# Tengu_v10.net
KiCad netlist of a schematic drawn in EAGLE
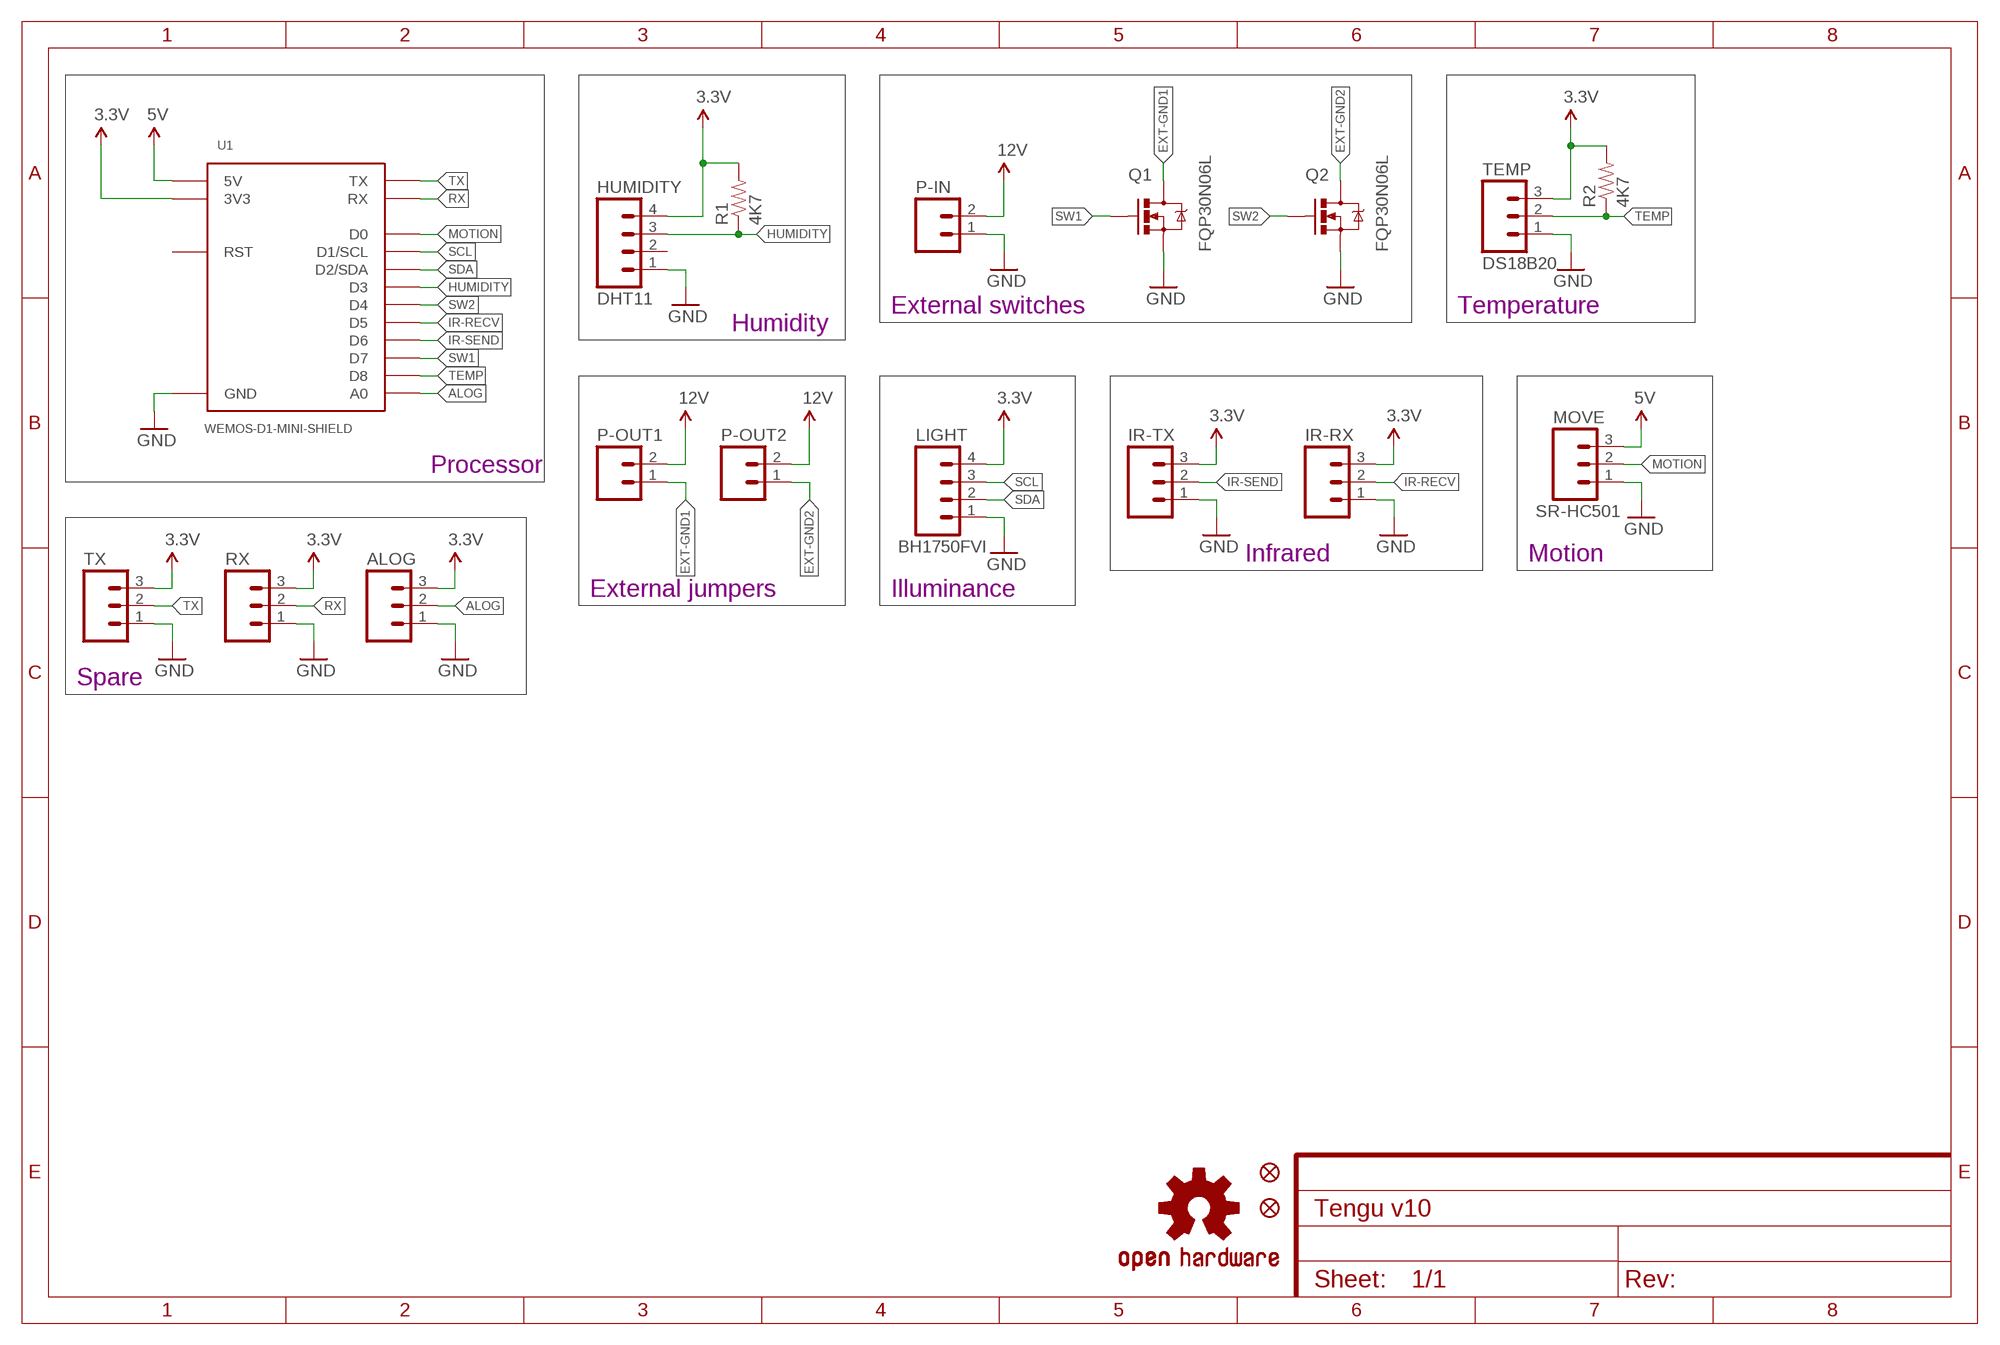
[diagram p0: schematic, sheet 1, part 1 of 2]
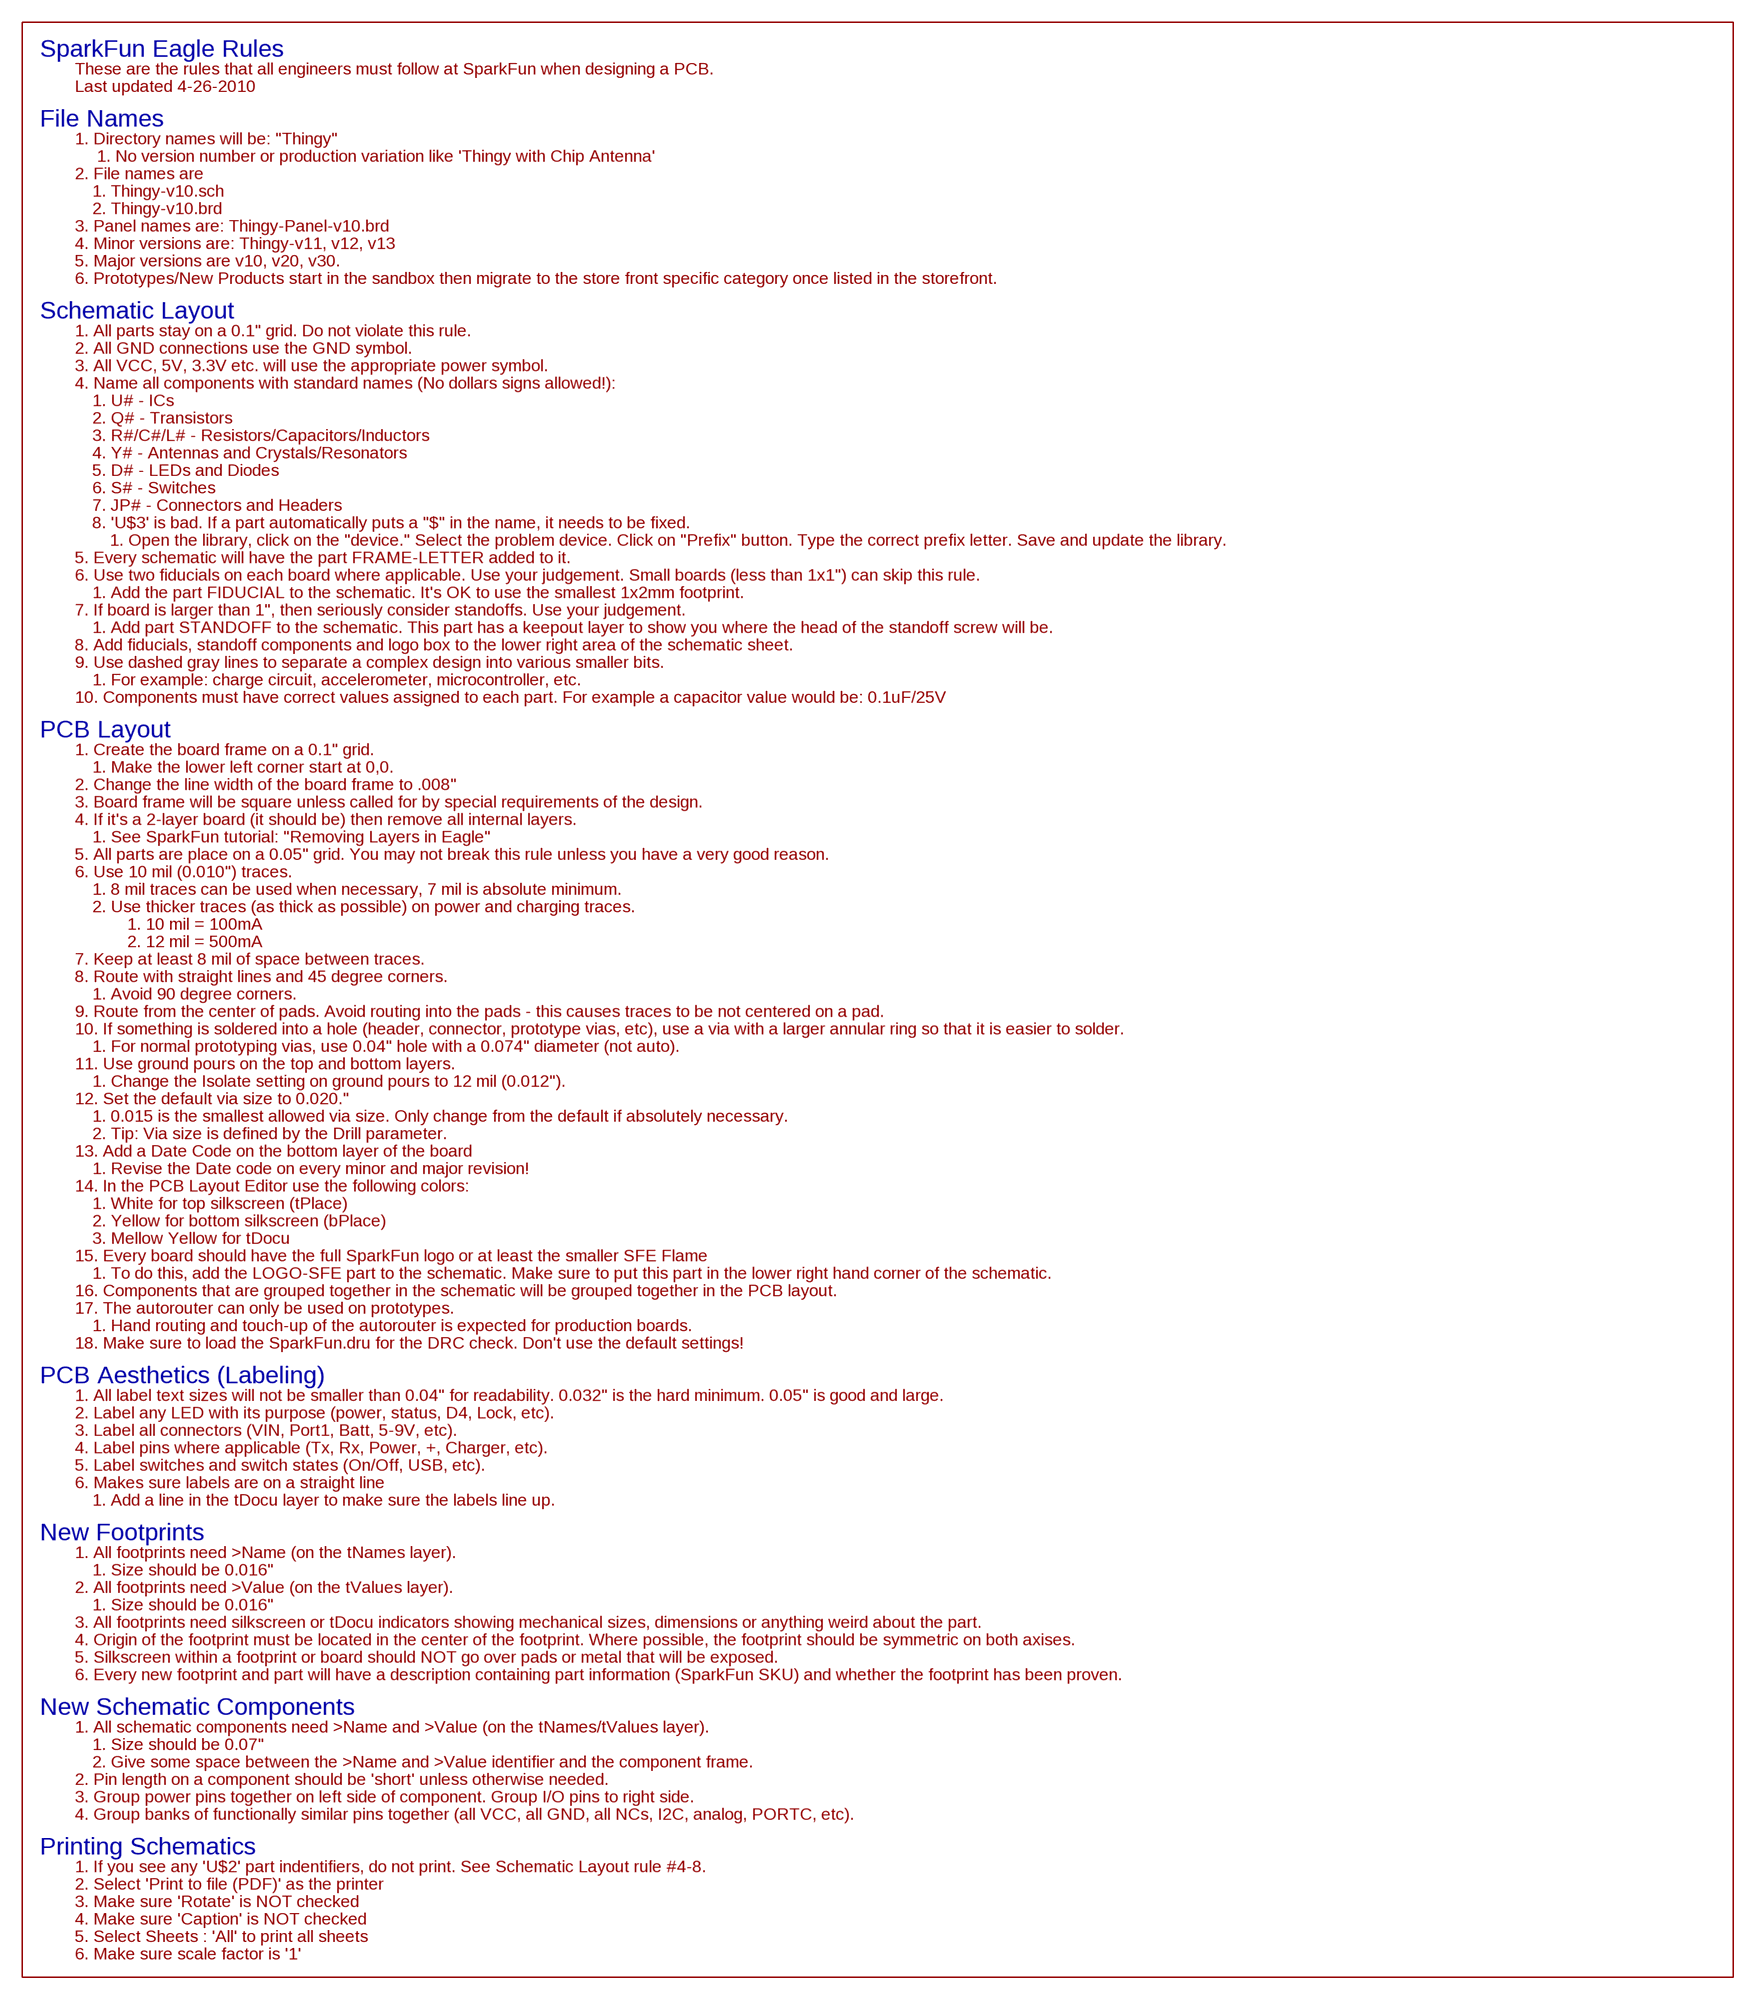
[diagram p1: schematic, sheet 1, part 2 of 2]

(export (version "E")
  (design (tool "Eeschema 10.0.6"))
  (components
    (comp (ref "ALOG")
      (value "M03PTH")
      (footprint "eagle-import:1X03")
      (libsource (lib "eagle-import") (part "M03PTH"))
    )
    (comp (ref "FD1")
      (value "FIDUCIAL1X2")
      (footprint "eagle-import:FIDUCIAL-1X2")
      (libsource (lib "eagle-import") (part "FIDUCIAL1X2"))
    )
    (comp (ref "FD2")
      (value "FIDUCIAL1X2")
      (footprint "eagle-import:FIDUCIAL-1X2")
      (libsource (lib "eagle-import") (part "FIDUCIAL1X2"))
    )
    (comp (ref "HUMIDITY")
      (value "DHT11")
      (footprint "eagle-import:1X04")
      (libsource (lib "eagle-import") (part "M04PTH"))
    )
    (comp (ref "IR-RX")
      (value "M03PTH")
      (footprint "eagle-import:1X03")
      (libsource (lib "eagle-import") (part "M03PTH"))
    )
    (comp (ref "IR-TX")
      (value "M03PTH")
      (footprint "eagle-import:1X03")
      (libsource (lib "eagle-import") (part "M03PTH"))
    )
    (comp (ref "LIGHT")
      (value "BH1750FVI")
      (footprint "eagle-import:1X04")
      (libsource (lib "eagle-import") (part "M04PTH"))
    )
    (comp (ref "LOGO1")
      (value "OSHW-LOGOM")
      (footprint "eagle-import:OSHW-LOGO-M")
      (libsource (lib "eagle-import") (part "OSHW-LOGOM"))
    )
    (comp (ref "MOVE")
      (value "SR-HC501")
      (footprint "eagle-import:1X03")
      (libsource (lib "eagle-import") (part "M03PTH"))
    )
    (comp (ref "P-IN")
      (value "M02PTH3")
      (footprint "eagle-import:1X02_LONGPADS")
      (libsource (lib "eagle-import") (part "M02PTH3"))
    )
    (comp (ref "P-OUT1")
      (value "M02PTH3")
      (footprint "eagle-import:1X02_LONGPADS")
      (libsource (lib "eagle-import") (part "M02PTH3"))
    )
    (comp (ref "P-OUT2")
      (value "M02PTH3")
      (footprint "eagle-import:1X02_LONGPADS")
      (libsource (lib "eagle-import") (part "M02PTH3"))
    )
    (comp (ref "Q1")
      (value "FQP30N06L")
      (footprint "eagle-import:TO220V")
      (libsource (lib "eagle-import") (part "MOSFET-NCHANNELFQP30N06L"))
    )
    (comp (ref "Q2")
      (value "FQP30N06L")
      (footprint "eagle-import:TO220V")
      (libsource (lib "eagle-import") (part "MOSFET-NCHANNELFQP30N06L"))
    )
    (comp (ref "R1")
      (value "4K7")
      (footprint "eagle-import:1206")
      (libsource (lib "eagle-import") (part "RESISTOR1206"))
    )
    (comp (ref "R2")
      (value "4K7")
      (footprint "eagle-import:1206")
      (libsource (lib "eagle-import") (part "RESISTOR1206"))
    )
    (comp (ref "RX")
      (value "M03PTH")
      (footprint "eagle-import:1X03")
      (libsource (lib "eagle-import") (part "M03PTH"))
    )
    (comp (ref "TEMP")
      (value "DS18B20")
      (footprint "eagle-import:1X03")
      (libsource (lib "eagle-import") (part "M03PTH"))
    )
    (comp (ref "TX")
      (value "M03PTH")
      (footprint "eagle-import:1X03")
      (libsource (lib "eagle-import") (part "M03PTH"))
    )
    (comp (ref "U1")
      (value "WEMOS-D1-MINI-SHIELD")
      (footprint "eagle-import:WEMOS-D1-MINI-SHIELD")
      (libsource (lib "eagle-import") (part "WEMOS-D1-MINI-SHIELD"))
    )
  )
  (nets
    (net (code "1") (name "3.3V") (class "Default")
      (node (ref "ALOG") (pin "3") (pinfunction "3_3") (pintype "passive"))
      (node (ref "HUMIDITY") (pin "4") (pinfunction "4_4") (pintype "passive"))
      (node (ref "IR-RX") (pin "3") (pinfunction "3_3") (pintype "passive"))
      (node (ref "IR-TX") (pin "3") (pinfunction "3_3") (pintype "passive"))
      (node (ref "LIGHT") (pin "4") (pinfunction "4_4") (pintype "passive"))
      (node (ref "R1") (pin "2") (pinfunction "2_2") (pintype "passive"))
      (node (ref "R2") (pin "2") (pinfunction "2_2") (pintype "passive"))
      (node (ref "RX") (pin "3") (pinfunction "3_3") (pintype "passive"))
      (node (ref "TEMP") (pin "3") (pinfunction "3_3") (pintype "passive"))
      (node (ref "TX") (pin "3") (pinfunction "3_3") (pintype "passive"))
      (node (ref "U1") (pin "3V3") (pinfunction "3V3_3V3") (pintype "power_in"))
    )
    (net (code "2") (name "5V") (class "Default")
      (node (ref "MOVE") (pin "3") (pinfunction "3_3") (pintype "passive"))
      (node (ref "U1") (pin "5V") (pinfunction "5V_5V") (pintype "power_in"))
    )
    (net (code "3") (name "12V") (class "Default")
      (node (ref "P-IN") (pin "2") (pinfunction "2_2") (pintype "passive"))
      (node (ref "P-OUT1") (pin "2") (pinfunction "2_2") (pintype "passive"))
      (node (ref "P-OUT2") (pin "2") (pinfunction "2_2") (pintype "passive"))
    )
    (net (code "4") (name "ALOG") (class "Default")
      (node (ref "ALOG") (pin "2") (pinfunction "2_2") (pintype "passive"))
      (node (ref "U1") (pin "A0") (pinfunction "A0_A0") (pintype "bidirectional"))
    )
    (net (code "5") (name "EXT-GND1") (class "Default")
      (node (ref "P-OUT1") (pin "1") (pinfunction "1_1") (pintype "passive"))
      (node (ref "Q1") (pin "2") (pinfunction "D_2") (pintype "passive"))
    )
    (net (code "6") (name "EXT-GND2") (class "Default")
      (node (ref "P-OUT2") (pin "1") (pinfunction "1_1") (pintype "passive"))
      (node (ref "Q2") (pin "2") (pinfunction "D_2") (pintype "passive"))
    )
    (net (code "7") (name "GND") (class "Default")
      (node (ref "ALOG") (pin "1") (pinfunction "1_1") (pintype "passive"))
      (node (ref "HUMIDITY") (pin "1") (pinfunction "1_1") (pintype "passive"))
      (node (ref "IR-RX") (pin "1") (pinfunction "1_1") (pintype "passive"))
      (node (ref "IR-TX") (pin "1") (pinfunction "1_1") (pintype "passive"))
      (node (ref "LIGHT") (pin "1") (pinfunction "1_1") (pintype "passive"))
      (node (ref "MOVE") (pin "1") (pinfunction "1_1") (pintype "passive"))
      (node (ref "P-IN") (pin "1") (pinfunction "1_1") (pintype "passive"))
      (node (ref "Q1") (pin "3") (pinfunction "S_3") (pintype "passive"))
      (node (ref "Q2") (pin "3") (pinfunction "S_3") (pintype "passive"))
      (node (ref "RX") (pin "1") (pinfunction "1_1") (pintype "passive"))
      (node (ref "TEMP") (pin "1") (pinfunction "1_1") (pintype "passive"))
      (node (ref "TX") (pin "1") (pinfunction "1_1") (pintype "passive"))
      (node (ref "U1") (pin "GND") (pinfunction "GND_GND") (pintype "power_in"))
    )
    (net (code "8") (name "HUMIDITY") (class "Default")
      (node (ref "HUMIDITY") (pin "3") (pinfunction "3_3") (pintype "passive"))
      (node (ref "R1") (pin "1") (pinfunction "1_1") (pintype "passive"))
      (node (ref "U1") (pin "D3") (pinfunction "D3_D3") (pintype "bidirectional"))
    )
    (net (code "9") (name "IR-RECV") (class "Default")
      (node (ref "IR-RX") (pin "2") (pinfunction "2_2") (pintype "passive"))
      (node (ref "U1") (pin "D5") (pinfunction "D5_D5") (pintype "bidirectional"))
    )
    (net (code "10") (name "IR-SEND") (class "Default")
      (node (ref "IR-TX") (pin "2") (pinfunction "2_2") (pintype "passive"))
      (node (ref "U1") (pin "D6") (pinfunction "D6_D6") (pintype "bidirectional"))
    )
    (net (code "11") (name "MOTION") (class "Default")
      (node (ref "MOVE") (pin "2") (pinfunction "2_2") (pintype "passive"))
      (node (ref "U1") (pin "D0") (pinfunction "D0_D0") (pintype "bidirectional"))
    )
    (net (code "12") (name "RX") (class "Default")
      (node (ref "RX") (pin "2") (pinfunction "2_2") (pintype "passive"))
      (node (ref "U1") (pin "RX") (pinfunction "RX_RX") (pintype "bidirectional"))
    )
    (net (code "13") (name "SCL") (class "Default")
      (node (ref "LIGHT") (pin "3") (pinfunction "3_3") (pintype "passive"))
      (node (ref "U1") (pin "D1") (pinfunction "D1/SCL_D1") (pintype "bidirectional"))
    )
    (net (code "14") (name "SDA") (class "Default")
      (node (ref "LIGHT") (pin "2") (pinfunction "2_2") (pintype "passive"))
      (node (ref "U1") (pin "D2") (pinfunction "D2/SDA_D2") (pintype "bidirectional"))
    )
    (net (code "15") (name "SW1") (class "Default")
      (node (ref "Q1") (pin "1") (pinfunction "G_1") (pintype "passive"))
      (node (ref "U1") (pin "D7") (pinfunction "D7_D7") (pintype "bidirectional"))
    )
    (net (code "16") (name "SW2") (class "Default")
      (node (ref "Q2") (pin "1") (pinfunction "G_1") (pintype "passive"))
      (node (ref "U1") (pin "D4") (pinfunction "D4_D4") (pintype "bidirectional"))
    )
    (net (code "17") (name "TEMP") (class "Default")
      (node (ref "R2") (pin "1") (pinfunction "1_1") (pintype "passive"))
      (node (ref "TEMP") (pin "2") (pinfunction "2_2") (pintype "passive"))
      (node (ref "U1") (pin "D8") (pinfunction "D8_D8") (pintype "bidirectional"))
    )
    (net (code "18") (name "TX") (class "Default")
      (node (ref "TX") (pin "2") (pinfunction "2_2") (pintype "passive"))
      (node (ref "U1") (pin "TX") (pinfunction "TX_TX") (pintype "bidirectional"))
    )
    (net (code "19") (name "unconnected-(HUMIDITY-Pad2)") (class "Default")
      (node (ref "HUMIDITY") (pin "2") (pinfunction "2_2") (pintype "passive"))
    )
    (net (code "20") (name "unconnected-(U1-PadRST)") (class "Default")
      (node (ref "U1") (pin "RST") (pinfunction "RST_RST") (pintype "bidirectional"))
    )
  )
)
